# Sensors_and_display.net
KiCad netlist of a schematic drawn in Altium Designer
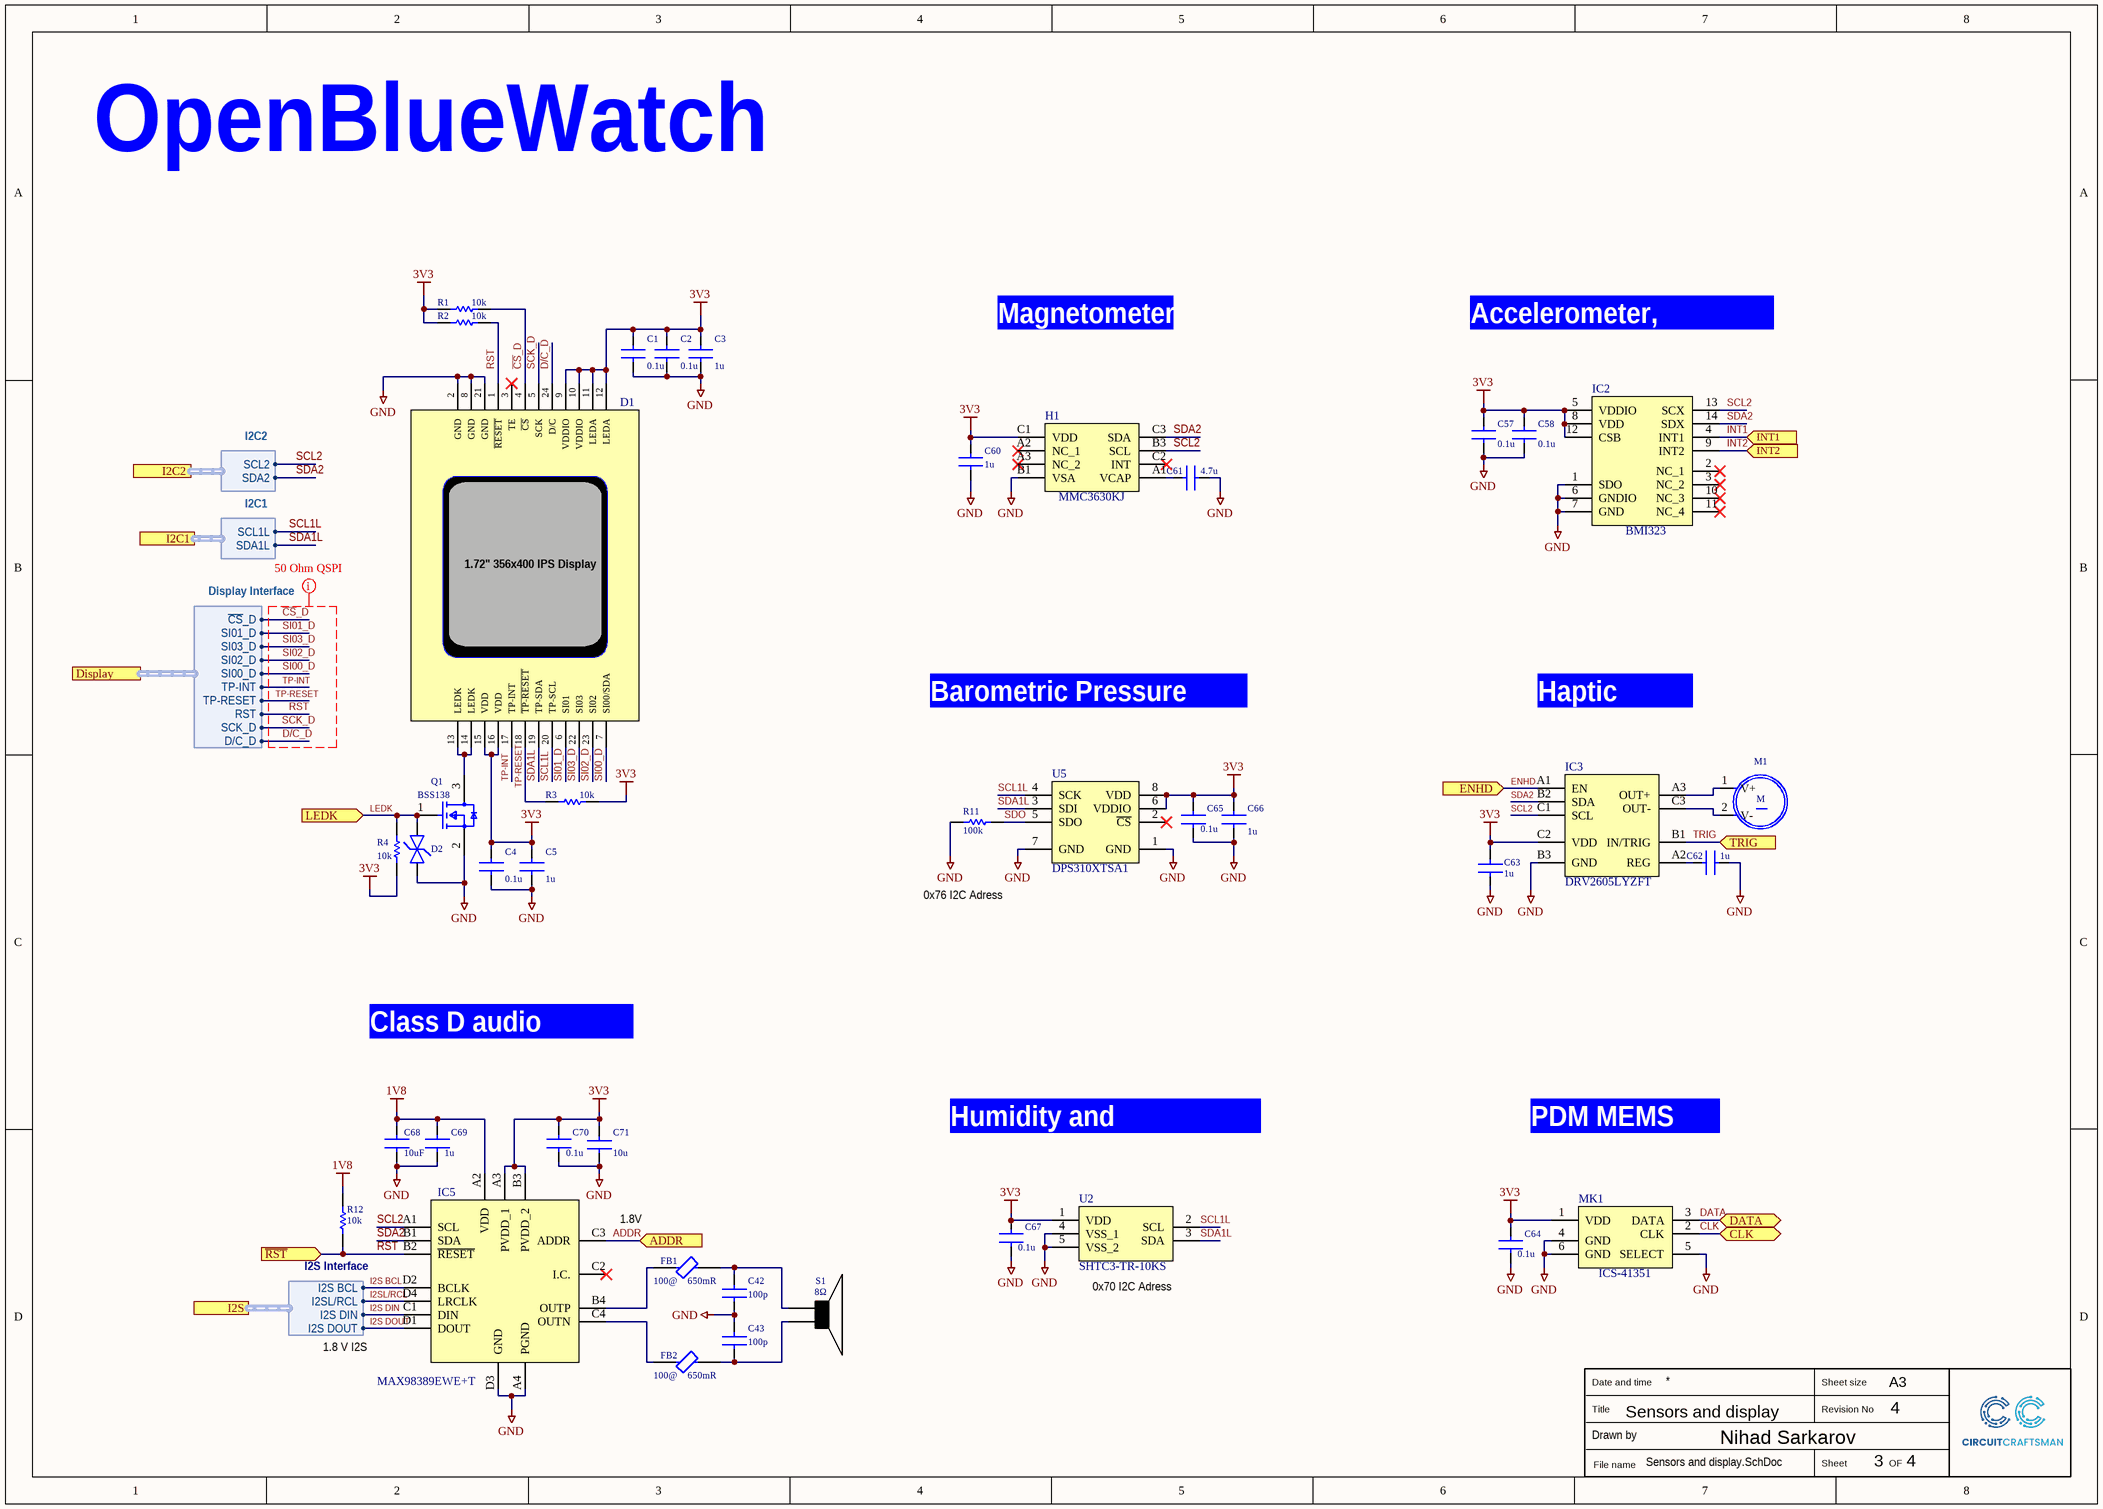
[diagram p0: Sensors and display.SchDoc]

(export (version "E")
  (design (tool "Eeschema 10.0.6"))
  (components
    (comp (ref "C1")
      (value "0.1u")
      (footprint "FP-CC0402-IPC_C")
      (description "CAP CER  X7R 0402")
      (fields (field (name "MANUFACTURER") "YAGEO") (field (name "TOLERANCE") "0.1"))
      (libsource (lib "Smart_Watch V4") (part "CMP-03422-000048-1"))
    )
    (comp (ref "C2")
      (value "0.1u")
      (footprint "FP-CC0402-IPC_C")
      (description "CAP CER  X7R 0402")
      (fields (field (name "MANUFACTURER") "YAGEO") (field (name "TOLERANCE") "0.1"))
      (libsource (lib "Smart_Watch V4") (part "CMP-03422-000048-1"))
    )
    (comp (ref "C3")
      (value "1u")
      (footprint "FP-CC0402-IPC_C")
      (description "CAP CER  X7R 0402")
      (fields (field (name "MANUFACTURER") "YAGEO") (field (name "TOLERANCE") "0.1"))
      (libsource (lib "Smart_Watch V4") (part "CMP-03422-000048-1"))
    )
    (comp (ref "C4")
      (value "0.1u")
      (footprint "FP-CC0402-IPC_C")
      (description "CAP CER  X7R 0402")
      (fields (field (name "MANUFACTURER") "YAGEO") (field (name "TOLERANCE") "0.1"))
      (libsource (lib "Smart_Watch V4") (part "CMP-03422-000048-1"))
    )
    (comp (ref "C5")
      (value "1u")
      (footprint "FP-CC0402-IPC_C")
      (description "CAP CER  X7R 0402")
      (fields (field (name "MANUFACTURER") "YAGEO") (field (name "TOLERANCE") "0.1"))
      (libsource (lib "Smart_Watch V4") (part "CMP-03422-000048-1"))
    )
    (comp (ref "C42")
      (value "100p")
      (footprint "FP-CC0201-BA-MFG")
      (description "CAP CER X7R 0201")
      (fields (field (name "TOLERANCE") "0.1") (field (name "MANUFACTURER PART NUMBER") "CC0201KRX7R8BB102"))
      (libsource (lib "Smart_Watch V4") (part "CMP-03422-000456-1"))
    )
    (comp (ref "C43")
      (value "100p")
      (footprint "FP-CC0201-BA-MFG")
      (description "CAP CER X7R 0201")
      (fields (field (name "TOLERANCE") "0.1") (field (name "MANUFACTURER PART NUMBER") "CC0201KRX7R8BB102"))
      (libsource (lib "Smart_Watch V4") (part "CMP-03422-000456-1"))
    )
    (comp (ref "C57")
      (value "0.1u")
      (footprint "FP-CC0201-BA-MFG")
      (description "CAP CER X7R 0201")
      (fields (field (name "TOLERANCE") "0.1") (field (name "MANUFACTURER PART NUMBER") "CC0201KRX7R8BB102"))
      (libsource (lib "Smart_Watch V4") (part "CMP-03422-000456-1"))
    )
    (comp (ref "C58")
      (value "0.1u")
      (footprint "FP-CC0201-BA-MFG")
      (description "CAP CER X7R 0201")
      (fields (field (name "TOLERANCE") "0.1") (field (name "MANUFACTURER PART NUMBER") "CC0201KRX7R8BB102"))
      (libsource (lib "Smart_Watch V4") (part "CMP-03422-000456-1"))
    )
    (comp (ref "C60")
      (value "1u")
      (footprint "FP-CC0402-IPC_C")
      (description "CAP CER  X7R 0402")
      (fields (field (name "MANUFACTURER") "YAGEO") (field (name "TOLERANCE") "0.1"))
      (libsource (lib "Smart_Watch V4") (part "CMP-03422-000048-1"))
    )
    (comp (ref "C61")
      (value "4.7u")
      (footprint "FP-CC0402-IPC_C")
      (description "CAP CER  X7R 0402")
      (fields (field (name "MANUFACTURER") "YAGEO") (field (name "TOLERANCE") "0.1"))
      (libsource (lib "Smart_Watch V4") (part "CMP-03422-000048-1"))
    )
    (comp (ref "C62")
      (value "1u")
      (footprint "FP-CC0402-IPC_C")
      (description "CAP CER  X7R 0402")
      (fields (field (name "MANUFACTURER") "YAGEO") (field (name "TOLERANCE") "0.1"))
      (libsource (lib "Smart_Watch V4") (part "CMP-03422-000048-1"))
    )
    (comp (ref "C63")
      (value "1u")
      (footprint "FP-CC0402-IPC_C")
      (description "CAP CER  X7R 0402")
      (fields (field (name "MANUFACTURER") "YAGEO") (field (name "TOLERANCE") "0.1"))
      (libsource (lib "Smart_Watch V4") (part "CMP-03422-000048-1"))
    )
    (comp (ref "C64")
      (value "0.1u")
      (footprint "FP-CC0201-BA-MFG")
      (description "CAP CER X7R 0201")
      (fields (field (name "TOLERANCE") "0.1") (field (name "MANUFACTURER PART NUMBER") "CC0201KRX7R8BB102"))
      (libsource (lib "Smart_Watch V4") (part "CMP-03422-000456-1"))
    )
    (comp (ref "C65")
      (value "0.1u")
      (footprint "FP-CC0201-BA-MFG")
      (description "CAP CER X7R 0201")
      (fields (field (name "TOLERANCE") "0.1") (field (name "MANUFACTURER PART NUMBER") "CC0201KRX7R8BB102"))
      (libsource (lib "Smart_Watch V4") (part "CMP-03422-000456-1"))
    )
    (comp (ref "C66")
      (value "1u")
      (footprint "FP-CC0402-IPC_C")
      (description "CAP CER  X7R 0402")
      (fields (field (name "MANUFACTURER") "YAGEO") (field (name "TOLERANCE") "0.1"))
      (libsource (lib "Smart_Watch V4") (part "CMP-03422-000048-1"))
    )
    (comp (ref "C67")
      (value "0.1u")
      (footprint "FP-CC0201-BA-MFG")
      (description "CAP CER X7R 0201")
      (fields (field (name "TOLERANCE") "0.1") (field (name "MANUFACTURER PART NUMBER") "CC0201KRX7R8BB102"))
      (libsource (lib "Smart_Watch V4") (part "CMP-03422-000456-1"))
    )
    (comp (ref "C68")
      (value "10uF")
      (footprint "FP-CC0402-IPC_C")
      (description "CAP CER  X7R 0402")
      (fields (field (name "MANUFACTURER") "YAGEO") (field (name "TOLERANCE") "0.1"))
      (libsource (lib "Smart_Watch V4") (part "CMP-03422-000048-1"))
    )
    (comp (ref "C69")
      (value "1u")
      (footprint "FP-CC0201-BA-MFG")
      (description "CAP CER X7R 0201")
      (fields (field (name "TOLERANCE") "0.1") (field (name "MANUFACTURER PART NUMBER") "CC0201KRX7R8BB102"))
      (libsource (lib "Smart_Watch V4") (part "CMP-03422-000456-1"))
    )
    (comp (ref "C70")
      (value "0.1u")
      (footprint "FP-CC0201-BA-MFG")
      (description "CAP CER X7R 0201")
      (fields (field (name "TOLERANCE") "0.1") (field (name "MANUFACTURER PART NUMBER") "CC0201KRX7R8BB102"))
      (libsource (lib "Smart_Watch V4") (part "CMP-03422-000456-1"))
    )
    (comp (ref "C71")
      (value "C1608X7R1E105K080AB")
      (footprint "FP-C1608-080-0_1-MFG")
      (description "Multilayer Ceramic Capacitors 1μF ±10% 25V X7R SMD 0603")
      (fields
        (field (name "CAPACITANCE") "10u")
        (field (name "TOLERANCE") "10%")
        (field (name "VOLTAGE") "25V")
      )
      (libsource (lib "Smart_Watch V4") (part "CMP-08246-005723-1"))
    )
    (comp (ref "D1")
      (value "1.72\" 356x400 IPS Display")
      (footprint "CONN-SMD_24P-P0.40_X0400FVS-24-LPSN")
      (description "1.72\" 356*400 IPS WAE2012 16.7M QSPI B2B Connector\r\n24 Pin – In Cell Touch")
      (libsource (lib "Smart_Watch V4") (part "1.72{dblquote} 356*400 IPS Display"))
    )
    (comp (ref "D2")
      (value "PGB1010402KR")
      (footprint "FP-PGB1-0402-IPC_A")
      (description "TVS DIODE 12V 250V 0402")
      (fields
        (field (name "OCTOPART") "https://octopart.com/pgb1010402kr-littelfuse-10444990")
        (field (name "MANUFACTURER") "Littelfuse")
      )
      (libsource (lib "Smart_Watch V4") (part "CMP-2000-05189-2"))
    )
    (comp (ref "FB1")
      (value "BLM15AG102SN1D")
      (footprint "FP-BLM15-0_05-IPC_A")
      (description "Chip Ferrite Bead, 0402, 1000Ω @ 100MHz, 0.65Ω, 25%, 300mA")
      (fields
        (field (name "TOLERANCE") "25%")
        (field (name "DC RESISTANCE (DCR)") "650mR")
        (field (name "FREQUENCY") "100@")
      )
      (libsource (lib "Smart_Watch V4") (part "CMP-0686-00181-5"))
    )
    (comp (ref "FB2")
      (value "BLM15AG102SN1D")
      (footprint "FP-BLM15-0_05-IPC_A")
      (description "Chip Ferrite Bead, 0402, 1000Ω @ 100MHz, 0.65Ω, 25%, 300mA")
      (fields
        (field (name "TOLERANCE") "25%")
        (field (name "DC RESISTANCE (DCR)") "650mR")
        (field (name "FREQUENCY") "100@")
      )
      (libsource (lib "Smart_Watch V4") (part "CMP-0686-00181-5"))
    )
    (comp (ref "H1")
      (value "MMC3630KJ")
      (footprint "SamacSys:BGA8C40P3X3_120X120X57")
      (description "MAGNETIC SENSOR 3-AXIS 1.2X1.2MM")
      (fields (field (name "MOUSER PART NUMBER") "438-MMC3630KJ"))
      (libsource (lib "Smart_Watch V4") (part "MMC3630KJ"))
    )
    (comp (ref "IC2")
      (value "BMI323")
      (footprint "SamacSys:BMI323")
      (description "Accelerometer, Gyroscope, 6 Axis Sensor I2C, I3C, SPI Output")
      (fields (field (name "DIGIKEY PART NUMBER") "828-BMI323TR-ND"))
      (libsource (lib "Smart_Watch V4") (part "BMI323"))
    )
    (comp (ref "IC3")
      (value "DRV2605LYZFT")
      (footprint "SamacSys:BGA9C50P3X3_144X144X62")
      (description "Motor Driver Power MOSFET I2C 9-DSBGA")
      (fields (field (name "MOUSER PART NUMBER") "595-DRV2605LYZFT"))
      (libsource (lib "Smart_Watch V4") (part "DRV2605LYZFT"))
    )
    (comp (ref "IC5")
      (value "MAX98389EWE+T")
      (footprint "SamacSys:BGA16C40P4X4_179X164X69")
      (description "Amplifier IC 1-Channel (Mono) Class D 16-WLP (1.64x1.79)")
      (fields (field (name "MANUFACTURER_PART_NUMBER") "MAX98389EWE+"))
      (libsource (lib "Smart_Watch V4") (part "MAX98389EWE+T"))
    )
    (comp (ref "M1")
      (value "NFP-WS0625")
      (footprint "NFP-WS0625")
      (description "6mm Brushless Coin Vibration Motor 2.5mm Type Motor")
      (libsource (lib "Smart_Watch V4") (part "NFP-WS0625"))
    )
    (comp (ref "MK1")
      (value "ICS-41351")
      (footprint "ICS-41351:MIC_ICS-41351")
      (fields (field (name "MF") "TDK InvenSense"))
      (libsource (lib "Smart_Watch V4") (part "ICS-41351"))
    )
    (comp (ref "Q1")
      (value "BSS138")
      (footprint "FP-318-08-IPC_B")
      (description "MOSFET N-CH 50V 220MA SOT-23")
      (libsource (lib "Altium Content Vault") (part "3b9c635fedb024a5347a57b145af9cc"))
    )
    (comp (ref "R1")
      (value "CRCW02010000Z0ED")
      (footprint "RESC0603X28X15LL5T05")
      (description "Chip Resistor, 0 Ohm, 0.05 W, -55 to 155 degC, 0201 (0603 Metric), RoHS, Tape and Reel")
      (fields (field (name "RESISTANCE") "10k") (field (name "TOLERANCE") "5%"))
      (libsource (lib "Smart_Watch V4") (part "CMP-2004-00001-2"))
    )
    (comp (ref "R2")
      (value "CRCW02010000Z0ED")
      (footprint "RESC0603X28X15LL5T05")
      (description "Chip Resistor, 0 Ohm, 0.05 W, -55 to 155 degC, 0201 (0603 Metric), RoHS, Tape and Reel")
      (fields (field (name "RESISTANCE") "10k") (field (name "TOLERANCE") "5%"))
      (libsource (lib "Smart_Watch V4") (part "CMP-2004-00001-2"))
    )
    (comp (ref "R3")
      (value "CRCW02010000Z0ED")
      (footprint "RESC0603X28X15LL5T05")
      (description "Chip Resistor, 0 Ohm, 0.05 W, -55 to 155 degC, 0201 (0603 Metric), RoHS, Tape and Reel")
      (fields (field (name "RESISTANCE") "10k") (field (name "TOLERANCE") "5%"))
      (libsource (lib "Smart_Watch V4") (part "CMP-2004-00001-2"))
    )
    (comp (ref "R4")
      (value "CRCW02010000Z0ED")
      (footprint "RESC0603X28X15LL5T05")
      (description "Chip Resistor, 0 Ohm, 0.05 W, -55 to 155 degC, 0201 (0603 Metric), RoHS, Tape and Reel")
      (fields (field (name "RESISTANCE") "10k") (field (name "TOLERANCE") "5%"))
      (libsource (lib "Smart_Watch V4") (part "CMP-2004-00001-2"))
    )
    (comp (ref "R11")
      (value "CRCW02010000Z0ED")
      (footprint "RESC0603X28X15LL5T05")
      (description "Chip Resistor, 0 Ohm, 0.05 W, -55 to 155 degC, 0201 (0603 Metric), RoHS, Tape and Reel")
      (fields (field (name "RESISTANCE") "100k") (field (name "TOLERANCE") "5%"))
      (libsource (lib "Smart_Watch V4") (part "CMP-2004-00001-2"))
    )
    (comp (ref "R12")
      (value "CRCW02010000Z0ED")
      (footprint "RESC0603X28X15LL5T05")
      (description "Chip Resistor, 0 Ohm, 0.05 W, -55 to 155 degC, 0201 (0603 Metric), RoHS, Tape and Reel")
      (fields (field (name "RESISTANCE") "10k") (field (name "TOLERANCE") "5%"))
      (libsource (lib "Smart_Watch V4") (part "CMP-2004-00001-2"))
    )
    (comp (ref "S1")
      (value "CMS-15118D-L100")
      (footprint "CMS-15118D-L100")
      (description "8 Ohms Low Profile Speaker 700 mW 425 Hz ~ 10 kHz Top Rectangular")
      (fields (field (name "IMPEDANCE") "8Ω"))
      (libsource (lib "Smart_Watch V4") (part "CMS-15118D-L100"))
    )
    (comp (ref "U2")
      (value "SHTC3-TR-10KS")
      (footprint "SamacSys:SHTC3TR10KS")
      (description "Humidity, Temperature 0 ~ 100% RH I2C ±2% RH 8 s Surface Mount")
      (fields (field (name "DIGIKEY PART NUMBER") "1649-SHTC3-TR-10KSTR-ND"))
      (libsource (lib "Smart_Watch V4") (part "SHTC3-TR-10KS"))
    )
    (comp (ref "U5")
      (value "DPS310XTSA1")
      (footprint "FP-PG-VLGA-8-MFG")
      (description "Pressure Sensor 4.35PSI ~ 17.4PSI (30kPa ~ 120kPa) Absolute 24 b 8-VFLGA")
      (libsource (lib "Smart_Watch V4") (part "CMP-32885-000002-2"))
    )
  )
  (nets
    (net (code "6") (name "/ADDR") (class "Default")
      (node (ref "IC5") (pin "C3") (pinfunction "ADDR_C3") (pintype "passive"))
    )
    (net (code "7") (name "/CLK") (class "Default")
      (node (ref "MK1") (pin "2") (pinfunction "CLK_2") (pintype "passive"))
    )
    (net (code "8") (name "/DATA") (class "Default")
      (node (ref "MK1") (pin "3") (pinfunction "DATA_3") (pintype "passive"))
    )
    (net (code "9") (name "/D{slash}C_D") (class "Default")
      (node (ref "D1") (pin "24") (pinfunction "D/C_24") (pintype "passive"))
    )
    (net (code "10") (name "/ENHD") (class "Default")
      (node (ref "IC3") (pin "A1") (pinfunction "EN_A1") (pintype "passive"))
    )
    (net (code "11") (name "/I2S BCL") (class "Default")
      (node (ref "IC5") (pin "D2") (pinfunction "BCLK_D2") (pintype "passive"))
    )
    (net (code "12") (name "/I2S DIN") (class "Default")
      (node (ref "IC5") (pin "C1") (pinfunction "DIN_C1") (pintype "passive"))
    )
    (net (code "13") (name "/I2S DOUT") (class "Default")
      (node (ref "IC5") (pin "D1") (pinfunction "DOUT_D1") (pintype "passive"))
    )
    (net (code "14") (name "/I2SL{slash}RCL") (class "Default")
      (node (ref "IC5") (pin "D4") (pinfunction "LRCLK_D4") (pintype "passive"))
    )
    (net (code "15") (name "/INT1") (class "Default")
      (node (ref "IC2") (pin "4") (pinfunction "INT1_4") (pintype "passive"))
    )
    (net (code "16") (name "/INT2") (class "Default")
      (node (ref "IC2") (pin "9") (pinfunction "INT2_9") (pintype "passive"))
    )
    (net (code "17") (name "/LEDK") (class "Default")
      (node (ref "D2") (pin "1") (pinfunction "1_1") (pintype "passive"))
      (node (ref "Q1") (pin "1") (pinfunction "G_1") (pintype "passive"))
      (node (ref "R4") (pin "1") (pinfunction "1_1") (pintype "passive"))
    )
    (net (code "18") (name "/RST") (class "Default")
      (node (ref "D1") (pin "1") (pinfunction "~{RESET}_1") (pintype "passive"))
      (node (ref "R2") (pin "1") (pinfunction "1_1") (pintype "passive"))
    )
    (net (code "19") (name "/SCK_D") (class "Default")
      (node (ref "D1") (pin "5") (pinfunction "SCK_5") (pintype "passive"))
    )
    (net (code "20") (name "/SCL1L") (class "Default")
      (node (ref "D1") (pin "20") (pinfunction "TP-SCL_20") (pintype "passive"))
      (node (ref "U2") (pin "2") (pinfunction "SCL_2") (pintype "passive"))
      (node (ref "U5") (pin "4") (pinfunction "SCK_4") (pintype "passive"))
    )
    (net (code "21") (name "/SCL2") (class "Default")
      (node (ref "H1") (pin "B3") (pinfunction "SCL_B3") (pintype "passive"))
      (node (ref "IC2") (pin "13") (pinfunction "SCX_13") (pintype "passive"))
      (node (ref "IC3") (pin "C1") (pinfunction "SCL_C1") (pintype "passive"))
      (node (ref "IC5") (pin "A1") (pinfunction "SCL_A1") (pintype "passive"))
    )
    (net (code "22") (name "/SDA1L") (class "Default")
      (node (ref "D1") (pin "19") (pinfunction "TP-SDA_19") (pintype "passive"))
      (node (ref "U2") (pin "3") (pinfunction "SDA_3") (pintype "passive"))
      (node (ref "U5") (pin "3") (pinfunction "SDI_3") (pintype "passive"))
    )
    (net (code "23") (name "/SDA2") (class "Default")
      (node (ref "H1") (pin "C3") (pinfunction "SDA_C3") (pintype "passive"))
      (node (ref "IC2") (pin "14") (pinfunction "SDX_14") (pintype "passive"))
      (node (ref "IC3") (pin "B2") (pinfunction "SDA_B2") (pintype "passive"))
      (node (ref "IC5") (pin "B1") (pinfunction "SDA_B1") (pintype "passive"))
    )
    (net (code "24") (name "/SDO") (class "Default")
      (node (ref "R11") (pin "1") (pinfunction "1_1") (pintype "passive"))
      (node (ref "U5") (pin "5") (pinfunction "SDO_5") (pintype "passive"))
    )
    (net (code "25") (name "/SI00_D") (class "Default")
      (node (ref "D1") (pin "7") (pinfunction "SI00/SDA_7") (pintype "passive"))
    )
    (net (code "26") (name "/SI01_D") (class "Default")
      (node (ref "D1") (pin "6") (pinfunction "SI01_6") (pintype "passive"))
    )
    (net (code "27") (name "/SI02_D") (class "Default")
      (node (ref "D1") (pin "23") (pinfunction "SI02_23") (pintype "passive"))
    )
    (net (code "28") (name "/SI03_D") (class "Default")
      (node (ref "D1") (pin "22") (pinfunction "SI03_22") (pintype "passive"))
    )
    (net (code "29") (name "/TP-INT") (class "Default")
      (node (ref "D1") (pin "17") (pinfunction "TP-INT_17") (pintype "passive"))
    )
    (net (code "30") (name "/TP-RESET") (class "Default")
      (node (ref "D1") (pin "18") (pinfunction "~{TP-RESET}_18") (pintype "passive"))
      (node (ref "R3") (pin "1") (pinfunction "1_1") (pintype "passive"))
    )
    (net (code "31") (name "/TRIG") (class "Default")
      (node (ref "IC3") (pin "B1") (pinfunction "IN/TRIG_B1") (pintype "passive"))
    )
    (net (code "36") (name "/~{CS}_D") (class "Default")
      (node (ref "D1") (pin "4") (pinfunction "~{CS}_4") (pintype "passive"))
      (node (ref "R1") (pin "1") (pinfunction "1_1") (pintype "passive"))
    )
    (net (code "37") (name "/~{RST}") (class "Default")
      (node (ref "IC5") (pin "B2") (pinfunction "~{RESET}_B2") (pintype "passive"))
      (node (ref "R12") (pin "2") (pinfunction "2_2") (pintype "passive"))
    )
    (net (code "38") (name "1V8") (class "Default")
      (node (ref "C68") (pin "1") (pinfunction "1_1") (pintype "passive"))
      (node (ref "C69") (pin "1") (pinfunction "1_1") (pintype "passive"))
      (node (ref "IC5") (pin "A2") (pinfunction "VDD_A2") (pintype "passive"))
      (node (ref "R12") (pin "1") (pinfunction "1_1") (pintype "passive"))
    )
    (net (code "39") (name "3V3") (class "Default")
      (node (ref "C1") (pin "1") (pinfunction "1_1") (pintype "passive"))
      (node (ref "C2") (pin "1") (pinfunction "1_1") (pintype "passive"))
      (node (ref "C3") (pin "1") (pinfunction "1_1") (pintype "passive"))
      (node (ref "C4") (pin "1") (pinfunction "1_1") (pintype "passive"))
      (node (ref "C5") (pin "1") (pinfunction "1_1") (pintype "passive"))
      (node (ref "C57") (pin "1") (pinfunction "1_1") (pintype "passive"))
      (node (ref "C58") (pin "1") (pinfunction "1_1") (pintype "passive"))
      (node (ref "C60") (pin "1") (pinfunction "1_1") (pintype "passive"))
      (node (ref "C63") (pin "2") (pinfunction "2_2") (pintype "passive"))
      (node (ref "C64") (pin "1") (pinfunction "1_1") (pintype "passive"))
      (node (ref "C65") (pin "1") (pinfunction "1_1") (pintype "passive"))
      (node (ref "C66") (pin "1") (pinfunction "1_1") (pintype "passive"))
      (node (ref "C67") (pin "1") (pinfunction "1_1") (pintype "passive"))
      (node (ref "C70") (pin "1") (pinfunction "1_1") (pintype "passive"))
      (node (ref "C71") (pin "2") (pinfunction "2_2") (pintype "passive"))
      (node (ref "D1") (pin "10") (pinfunction "VDDIO_10") (pintype "passive"))
      (node (ref "D1") (pin "11") (pinfunction "LEDA_11") (pintype "passive"))
      (node (ref "D1") (pin "12") (pinfunction "LEDA_12") (pintype "passive"))
      (node (ref "D1") (pin "15") (pinfunction "VDD_15") (pintype "passive"))
      (node (ref "D1") (pin "16") (pinfunction "VDD_16") (pintype "passive"))
      (node (ref "D1") (pin "9") (pinfunction "VDDIO_9") (pintype "passive"))
      (node (ref "H1") (pin "C1") (pinfunction "VDD_C1") (pintype "passive"))
      (node (ref "IC2") (pin "12") (pinfunction "CSB_12") (pintype "passive"))
      (node (ref "IC2") (pin "5") (pinfunction "VDDIO_5") (pintype "passive"))
      (node (ref "IC2") (pin "8") (pinfunction "VDD_8") (pintype "passive"))
      (node (ref "IC3") (pin "C2") (pinfunction "VDD_C2") (pintype "passive"))
      (node (ref "IC5") (pin "A3") (pinfunction "PVDD_1_A3") (pintype "passive"))
      (node (ref "IC5") (pin "B3") (pinfunction "PVDD_2_B3") (pintype "passive"))
      (node (ref "MK1") (pin "1") (pinfunction "VDD_1") (pintype "power_in"))
      (node (ref "R1") (pin "2") (pinfunction "2_2") (pintype "passive"))
      (node (ref "R2") (pin "2") (pinfunction "2_2") (pintype "passive"))
      (node (ref "R3") (pin "2") (pinfunction "2_2") (pintype "passive"))
      (node (ref "R4") (pin "2") (pinfunction "2_2") (pintype "passive"))
      (node (ref "U2") (pin "1") (pinfunction "VDD_1") (pintype "passive"))
      (node (ref "U5") (pin "6") (pinfunction "VDDIO_6") (pintype "passive"))
      (node (ref "U5") (pin "8") (pinfunction "VDD_8") (pintype "passive"))
    )
    (net (code "40") (name "GND") (class "Default")
      (node (ref "C1") (pin "2") (pinfunction "2_2") (pintype "passive"))
      (node (ref "C2") (pin "2") (pinfunction "2_2") (pintype "passive"))
      (node (ref "C3") (pin "2") (pinfunction "2_2") (pintype "passive"))
      (node (ref "C4") (pin "2") (pinfunction "2_2") (pintype "passive"))
      (node (ref "C42") (pin "1") (pinfunction "1_1") (pintype "passive"))
      (node (ref "C43") (pin "2") (pinfunction "2_2") (pintype "passive"))
      (node (ref "C5") (pin "2") (pinfunction "2_2") (pintype "passive"))
      (node (ref "C57") (pin "2") (pinfunction "2_2") (pintype "passive"))
      (node (ref "C58") (pin "2") (pinfunction "2_2") (pintype "passive"))
      (node (ref "C60") (pin "2") (pinfunction "2_2") (pintype "passive"))
      (node (ref "C61") (pin "2") (pinfunction "2_2") (pintype "passive"))
      (node (ref "C62") (pin "2") (pinfunction "2_2") (pintype "passive"))
      (node (ref "C63") (pin "1") (pinfunction "1_1") (pintype "passive"))
      (node (ref "C64") (pin "2") (pinfunction "2_2") (pintype "passive"))
      (node (ref "C65") (pin "2") (pinfunction "2_2") (pintype "passive"))
      (node (ref "C66") (pin "2") (pinfunction "2_2") (pintype "passive"))
      (node (ref "C67") (pin "2") (pinfunction "2_2") (pintype "passive"))
      (node (ref "C68") (pin "2") (pinfunction "2_2") (pintype "passive"))
      (node (ref "C69") (pin "2") (pinfunction "2_2") (pintype "passive"))
      (node (ref "C70") (pin "2") (pinfunction "2_2") (pintype "passive"))
      (node (ref "C71") (pin "1") (pinfunction "1_1") (pintype "passive"))
      (node (ref "D1") (pin "2") (pinfunction "GND_2") (pintype "passive"))
      (node (ref "D1") (pin "21") (pinfunction "GND_21") (pintype "passive"))
      (node (ref "D1") (pin "8") (pinfunction "GND_8") (pintype "passive"))
      (node (ref "D2") (pin "2") (pinfunction "2_2") (pintype "passive"))
      (node (ref "H1") (pin "B1") (pinfunction "VSA_B1") (pintype "power_in"))
      (node (ref "IC2") (pin "1") (pinfunction "SDO_1") (pintype "passive"))
      (node (ref "IC2") (pin "6") (pinfunction "GNDIO_6") (pintype "passive"))
      (node (ref "IC2") (pin "7") (pinfunction "GND_7") (pintype "passive"))
      (node (ref "IC3") (pin "B3") (pinfunction "GND_B3") (pintype "passive"))
      (node (ref "IC5") (pin "A4") (pinfunction "PGND_A4") (pintype "passive"))
      (node (ref "IC5") (pin "D3") (pinfunction "GND_D3") (pintype "passive"))
      (node (ref "MK1") (pin "4") (pinfunction "GND_4") (pintype "power_in"))
      (node (ref "MK1") (pin "5") (pinfunction "SELECT_5") (pintype "passive"))
      (node (ref "MK1") (pin "6") (pinfunction "GND_6") (pintype "power_in"))
      (node (ref "Q1") (pin "2") (pinfunction "S_2") (pintype "passive"))
      (node (ref "R11") (pin "2") (pinfunction "2_2") (pintype "passive"))
      (node (ref "U2") (pin "4") (pinfunction "VSS_1_4") (pintype "passive"))
      (node (ref "U2") (pin "5") (pinfunction "VSS_2_5") (pintype "passive"))
      (node (ref "U5") (pin "1") (pinfunction "GND_1") (pintype "passive"))
      (node (ref "U5") (pin "7") (pinfunction "GND_7") (pintype "passive"))
    )
    (net (code "41") (name "Net-(H1-VCAP)") (class "Default")
      (node (ref "C61") (pin "1") (pinfunction "1_1") (pintype "passive"))
      (node (ref "H1") (pin "A1") (pinfunction "VCAP_A1") (pintype "power_in"))
    )
    (net (code "42") (name "Net-(IC3-OUT+)") (class "Default")
      (node (ref "IC3") (pin "A3") (pinfunction "OUT+_A3") (pintype "passive"))
      (node (ref "M1") (pin "1") (pinfunction "V+_1") (pintype "power_in"))
    )
    (net (code "43") (name "Net-(IC3-OUT-)") (class "Default")
      (node (ref "IC3") (pin "C3") (pinfunction "OUT-_C3") (pintype "passive"))
      (node (ref "M1") (pin "2") (pinfunction "V-_2") (pintype "power_in"))
    )
    (net (code "44") (name "Net-(IC3-REG)") (class "Default")
      (node (ref "C62") (pin "1") (pinfunction "1_1") (pintype "passive"))
      (node (ref "IC3") (pin "A2") (pinfunction "REG_A2") (pintype "passive"))
    )
    (net (code "45") (name "Net-(IC5-OUTN)") (class "Default")
      (node (ref "FB2") (pin "1") (pinfunction "1_1") (pintype "passive"))
      (node (ref "IC5") (pin "C4") (pinfunction "OUTN_C4") (pintype "passive"))
    )
    (net (code "46") (name "Net-(IC5-OUTP)") (class "Default")
      (node (ref "FB1") (pin "1") (pinfunction "1_1") (pintype "passive"))
      (node (ref "IC5") (pin "B4") (pinfunction "OUTP_B4") (pintype "passive"))
    )
    (net (code "47") (name "Net-(Q1-D)") (class "Default")
      (node (ref "D1") (pin "13") (pinfunction "LEDK_13") (pintype "passive"))
      (node (ref "D1") (pin "14") (pinfunction "LEDK_14") (pintype "passive"))
      (node (ref "Q1") (pin "3") (pinfunction "D_3") (pintype "passive"))
    )
    (net (code "48") (name "Net-(S1-+)") (class "Default")
      (node (ref "C42") (pin "2") (pinfunction "2_2") (pintype "passive"))
      (node (ref "FB1") (pin "2") (pinfunction "2_2") (pintype "passive"))
      (node (ref "S1") (pin "1") (pinfunction "+_1") (pintype "passive"))
    )
    (net (code "49") (name "Net-(S1--)") (class "Default")
      (node (ref "C43") (pin "1") (pinfunction "1_1") (pintype "passive"))
      (node (ref "FB2") (pin "2") (pinfunction "2_2") (pintype "passive"))
      (node (ref "S1") (pin "2") (pinfunction "-_2") (pintype "passive"))
    )
    (net (code "50") (name "unconnected-(D1-TE-Pad3)") (class "Default")
      (node (ref "D1") (pin "3") (pinfunction "TE_3") (pintype "passive+no_connect"))
    )
    (net (code "51") (name "unconnected-(H1-INT-PadC2)") (class "Default")
      (node (ref "H1") (pin "C2") (pinfunction "INT_C2") (pintype "passive+no_connect"))
    )
    (net (code "52") (name "unconnected-(H1-NC_1-PadA2)") (class "Default")
      (node (ref "H1") (pin "A2") (pinfunction "NC_1_A2") (pintype "passive+no_connect"))
    )
    (net (code "53") (name "unconnected-(H1-NC_2-PadA3)") (class "Default")
      (node (ref "H1") (pin "A3") (pinfunction "NC_2_A3") (pintype "passive+no_connect"))
    )
    (net (code "54") (name "unconnected-(IC2-NC_1-Pad2)") (class "Default")
      (node (ref "IC2") (pin "2") (pinfunction "NC_1_2") (pintype "passive+no_connect"))
    )
    (net (code "55") (name "unconnected-(IC2-NC_2-Pad3)") (class "Default")
      (node (ref "IC2") (pin "3") (pinfunction "NC_2_3") (pintype "passive+no_connect"))
    )
    (net (code "56") (name "unconnected-(IC2-NC_3-Pad10)") (class "Default")
      (node (ref "IC2") (pin "10") (pinfunction "NC_3_10") (pintype "passive+no_connect"))
    )
    (net (code "57") (name "unconnected-(IC2-NC_4-Pad11)") (class "Default")
      (node (ref "IC2") (pin "11") (pinfunction "NC_4_11") (pintype "passive+no_connect"))
    )
    (net (code "58") (name "unconnected-(IC5-I.C.-PadC2)") (class "Default")
      (node (ref "IC5") (pin "C2") (pinfunction "I.C._C2") (pintype "passive+no_connect"))
    )
    (net (code "59") (name "unconnected-(U5-~{CS}-Pad2)") (class "Default")
      (node (ref "U5") (pin "2") (pinfunction "~{CS}_2") (pintype "passive+no_connect"))
    )
  )
)
